# LedMatrix-595.net
KiCad netlist of a schematic drawn in EAGLE
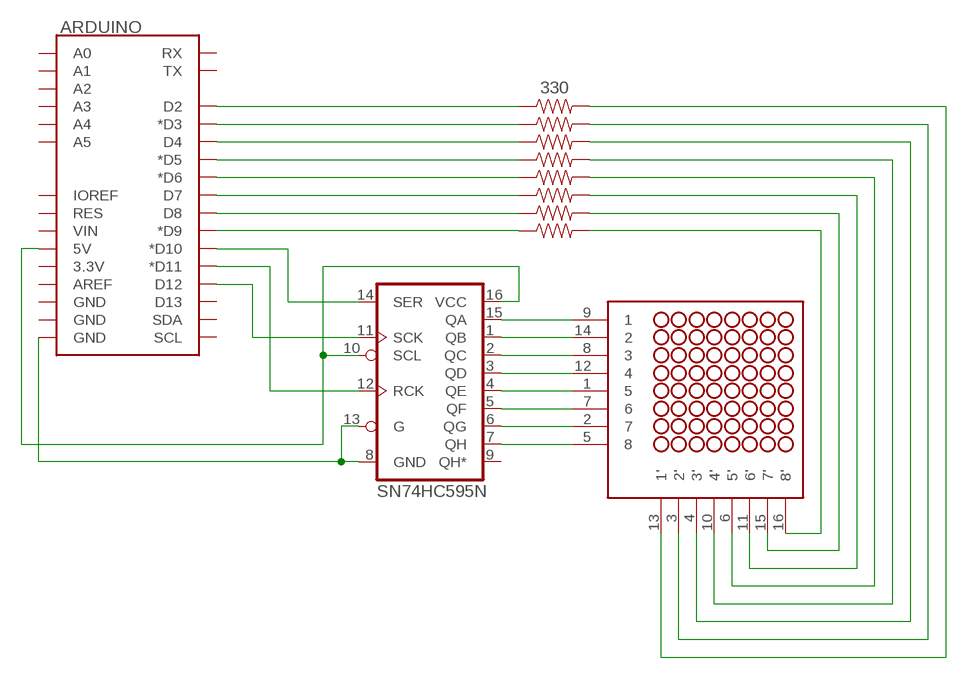
[diagram p0: schematic, sheet 1]

(export (version "E")
  (design (tool "Eeschema 10.0.6"))
  (components
    (comp (ref "ARDUINO")
      (value "ARDUINO_UNO_R3_SHIELDBASIC")
      (footprint "eagle-import:UNO_R3_SHIELD")
      (libsource (lib "eagle-import") (part "ARDUINO_UNO_R3_SHIELDBASIC"))
    )
    (comp (ref "R1")
      (value "330")
      (footprint "eagle-import:AXIAL-0.3")
      (libsource (lib "eagle-import") (part "330OHM-HORIZ-1/10W-5%"))
    )
    (comp (ref "R2")
      (value "330")
      (footprint "eagle-import:AXIAL-0.3")
      (libsource (lib "eagle-import") (part "330OHM-HORIZ-1/10W-5%"))
    )
    (comp (ref "R3")
      (value "330")
      (footprint "eagle-import:AXIAL-0.3")
      (libsource (lib "eagle-import") (part "330OHM-HORIZ-1/10W-5%"))
    )
    (comp (ref "R4")
      (value "330")
      (footprint "eagle-import:AXIAL-0.3")
      (libsource (lib "eagle-import") (part "330OHM-HORIZ-1/10W-5%"))
    )
    (comp (ref "R5")
      (value "330")
      (footprint "eagle-import:AXIAL-0.3")
      (libsource (lib "eagle-import") (part "330OHM-HORIZ-1/10W-5%"))
    )
    (comp (ref "R6")
      (value "330")
      (footprint "eagle-import:AXIAL-0.3")
      (libsource (lib "eagle-import") (part "330OHM-HORIZ-1/10W-5%"))
    )
    (comp (ref "R7")
      (value "330")
      (footprint "eagle-import:AXIAL-0.3")
      (libsource (lib "eagle-import") (part "330OHM-HORIZ-1/10W-5%"))
    )
    (comp (ref "R8")
      (value "330")
      (footprint "eagle-import:AXIAL-0.3")
      (libsource (lib "eagle-import") (part "330OHM-HORIZ-1/10W-5%"))
    )
    (comp (ref "U$1")
      (value "NFM-12881BG-11")
      (footprint "eagle-import:NFM-12881BG-11")
      (libsource (lib "eagle-import") (part "NFM-12881BG-11"))
    )
    (comp (ref "U1")
      (value "SN74HC595N")
      (footprint "eagle-import:DIP16")
      (libsource (lib "eagle-import") (part "74595NHC"))
    )
  )
  (nets
    (net (code "1") (name "Net-(ARDUINO-*D3)") (class "Default")
      (node (ref "ARDUINO") (pin "D3") (pinfunction "*D3_D3") (pintype "bidirectional"))
      (node (ref "R2") (pin "P$1") (pinfunction "1_P$1") (pintype "passive"))
    )
    (net (code "2") (name "Net-(ARDUINO-*D5)") (class "Default")
      (node (ref "ARDUINO") (pin "D5") (pinfunction "*D5_D5") (pintype "bidirectional"))
      (node (ref "R4") (pin "P$1") (pinfunction "1_P$1") (pintype "passive"))
    )
    (net (code "3") (name "Net-(ARDUINO-*D6)") (class "Default")
      (node (ref "ARDUINO") (pin "D6") (pinfunction "*D6_D6") (pintype "bidirectional"))
      (node (ref "R5") (pin "P$1") (pinfunction "1_P$1") (pintype "passive"))
    )
    (net (code "4") (name "Net-(ARDUINO-*D9)") (class "Default")
      (node (ref "ARDUINO") (pin "D9") (pinfunction "*D9_D9") (pintype "bidirectional"))
      (node (ref "R8") (pin "P$1") (pinfunction "1_P$1") (pintype "passive"))
    )
    (net (code "5") (name "Net-(ARDUINO-*D10)") (class "Default")
      (node (ref "ARDUINO") (pin "D10") (pinfunction "*D10_D10") (pintype "bidirectional"))
      (node (ref "U1") (pin "14") (pinfunction "SER_14") (pintype "input"))
    )
    (net (code "6") (name "Net-(ARDUINO-*D11)") (class "Default")
      (node (ref "ARDUINO") (pin "D11") (pinfunction "*D11_D11") (pintype "bidirectional"))
      (node (ref "U1") (pin "12") (pinfunction "RCK_12") (pintype "input"))
    )
    (net (code "7") (name "Net-(R1-1)") (class "Default")
      (node (ref "ARDUINO") (pin "D2") (pinfunction "D2_D2") (pintype "bidirectional"))
      (node (ref "R1") (pin "P$1") (pinfunction "1_P$1") (pintype "passive"))
    )
    (net (code "8") (name "Net-(R1-2)") (class "Default")
      (node (ref "R1") (pin "P$2") (pinfunction "2_P$2") (pintype "passive"))
      (node (ref "U$1") (pin "13") (pinfunction "1'_13") (pintype "output"))
    )
    (net (code "9") (name "Net-(R2-2)") (class "Default")
      (node (ref "R2") (pin "P$2") (pinfunction "2_P$2") (pintype "passive"))
      (node (ref "U$1") (pin "3") (pinfunction "2'_3") (pintype "output"))
    )
    (net (code "10") (name "Net-(R3-1)") (class "Default")
      (node (ref "ARDUINO") (pin "D4") (pinfunction "D4_D4") (pintype "bidirectional"))
      (node (ref "R3") (pin "P$1") (pinfunction "1_P$1") (pintype "passive"))
    )
    (net (code "11") (name "Net-(R3-2)") (class "Default")
      (node (ref "R3") (pin "P$2") (pinfunction "2_P$2") (pintype "passive"))
      (node (ref "U$1") (pin "4") (pinfunction "3'_4") (pintype "output"))
    )
    (net (code "12") (name "Net-(R4-2)") (class "Default")
      (node (ref "R4") (pin "P$2") (pinfunction "2_P$2") (pintype "passive"))
      (node (ref "U$1") (pin "10") (pinfunction "4'_10") (pintype "output"))
    )
    (net (code "13") (name "Net-(R5-2)") (class "Default")
      (node (ref "R5") (pin "P$2") (pinfunction "2_P$2") (pintype "passive"))
      (node (ref "U$1") (pin "6") (pinfunction "5'_6") (pintype "output"))
    )
    (net (code "14") (name "Net-(R6-1)") (class "Default")
      (node (ref "ARDUINO") (pin "D7") (pinfunction "D7_D7") (pintype "bidirectional"))
      (node (ref "R6") (pin "P$1") (pinfunction "1_P$1") (pintype "passive"))
    )
    (net (code "15") (name "Net-(R6-2)") (class "Default")
      (node (ref "R6") (pin "P$2") (pinfunction "2_P$2") (pintype "passive"))
      (node (ref "U$1") (pin "11") (pinfunction "6'_11") (pintype "output"))
    )
    (net (code "16") (name "Net-(R7-1)") (class "Default")
      (node (ref "ARDUINO") (pin "D8") (pinfunction "D8_D8") (pintype "bidirectional"))
      (node (ref "R7") (pin "P$1") (pinfunction "1_P$1") (pintype "passive"))
    )
    (net (code "17") (name "Net-(R7-2)") (class "Default")
      (node (ref "R7") (pin "P$2") (pinfunction "2_P$2") (pintype "passive"))
      (node (ref "U$1") (pin "15") (pinfunction "7'_15") (pintype "output"))
    )
    (net (code "18") (name "Net-(R8-2)") (class "Default")
      (node (ref "R8") (pin "P$2") (pinfunction "2_P$2") (pintype "passive"))
      (node (ref "U$1") (pin "16") (pinfunction "8'_16") (pintype "output"))
    )
    (net (code "19") (name "Net-(U$1-1)") (class "Default")
      (node (ref "U$1") (pin "9") (pinfunction "1_9") (pintype "input"))
      (node (ref "U1") (pin "15") (pinfunction "QA_15") (pintype "tri_state"))
    )
    (net (code "20") (name "Net-(U$1-2)") (class "Default")
      (node (ref "U$1") (pin "14") (pinfunction "2_14") (pintype "input"))
      (node (ref "U1") (pin "1") (pinfunction "QB_1") (pintype "tri_state"))
    )
    (net (code "21") (name "Net-(U$1-3)") (class "Default")
      (node (ref "U$1") (pin "8") (pinfunction "3_8") (pintype "input"))
      (node (ref "U1") (pin "2") (pinfunction "QC_2") (pintype "tri_state"))
    )
    (net (code "22") (name "Net-(U$1-4)") (class "Default")
      (node (ref "U$1") (pin "12") (pinfunction "4_12") (pintype "input"))
      (node (ref "U1") (pin "3") (pinfunction "QD_3") (pintype "tri_state"))
    )
    (net (code "23") (name "Net-(U$1-5)") (class "Default")
      (node (ref "U$1") (pin "1") (pinfunction "5_1") (pintype "input"))
      (node (ref "U1") (pin "4") (pinfunction "QE_4") (pintype "tri_state"))
    )
    (net (code "24") (name "Net-(U$1-6)") (class "Default")
      (node (ref "U$1") (pin "7") (pinfunction "6_7") (pintype "input"))
      (node (ref "U1") (pin "5") (pinfunction "QF_5") (pintype "tri_state"))
    )
    (net (code "25") (name "Net-(U$1-7)") (class "Default")
      (node (ref "U$1") (pin "2") (pinfunction "7_2") (pintype "input"))
      (node (ref "U1") (pin "6") (pinfunction "QG_6") (pintype "tri_state"))
    )
    (net (code "26") (name "Net-(U$1-8)") (class "Default")
      (node (ref "U$1") (pin "5") (pinfunction "8_5") (pintype "input"))
      (node (ref "U1") (pin "7") (pinfunction "QH_7") (pintype "tri_state"))
    )
    (net (code "27") (name "Net-(U1-G)") (class "Default")
      (node (ref "ARDUINO") (pin "GND@0") (pinfunction "GND_GND@0") (pintype "bidirectional"))
      (node (ref "U1") (pin "13") (pinfunction "G_13") (pintype "input"))
      (node (ref "U1") (pin "8") (pinfunction "GND_8") (pintype "power_in"))
    )
    (net (code "28") (name "Net-(U1-SCK)") (class "Default")
      (node (ref "ARDUINO") (pin "D12") (pinfunction "D12_D12") (pintype "bidirectional"))
      (node (ref "U1") (pin "11") (pinfunction "SCK_11") (pintype "input"))
    )
    (net (code "29") (name "Net-(U1-SCL)") (class "Default")
      (node (ref "ARDUINO") (pin "5V") (pinfunction "5V_5V") (pintype "bidirectional"))
      (node (ref "U1") (pin "10") (pinfunction "SCL_10") (pintype "input"))
      (node (ref "U1") (pin "16") (pinfunction "VCC_16") (pintype "power_in"))
    )
    (net (code "30") (name "unconnected-(ARDUINO-GND-PadGND@1)") (class "Default")
      (node (ref "ARDUINO") (pin "GND@1") (pinfunction "GND_GND@1") (pintype "bidirectional"))
    )
    (net (code "31") (name "unconnected-(ARDUINO-GND-PadGND@2)") (class "Default")
      (node (ref "ARDUINO") (pin "GND@2") (pinfunction "GND_GND@2") (pintype "bidirectional"))
    )
    (net (code "32") (name "unconnected-(ARDUINO-Pad3.3V)") (class "Default")
      (node (ref "ARDUINO") (pin "3.3V") (pinfunction "3.3V_3.3V") (pintype "bidirectional"))
    )
    (net (code "33") (name "unconnected-(ARDUINO-PadA0)") (class "Default")
      (node (ref "ARDUINO") (pin "A0") (pinfunction "A0_A0") (pintype "bidirectional"))
    )
    (net (code "34") (name "unconnected-(ARDUINO-PadA1)") (class "Default")
      (node (ref "ARDUINO") (pin "A1") (pinfunction "A1_A1") (pintype "bidirectional"))
    )
    (net (code "35") (name "unconnected-(ARDUINO-PadA2)") (class "Default")
      (node (ref "ARDUINO") (pin "A2") (pinfunction "A2_A2") (pintype "bidirectional"))
    )
    (net (code "36") (name "unconnected-(ARDUINO-PadA3)") (class "Default")
      (node (ref "ARDUINO") (pin "A3") (pinfunction "A3_A3") (pintype "bidirectional"))
    )
    (net (code "37") (name "unconnected-(ARDUINO-PadA4)") (class "Default")
      (node (ref "ARDUINO") (pin "A4") (pinfunction "A4_A4") (pintype "bidirectional"))
    )
    (net (code "38") (name "unconnected-(ARDUINO-PadA5)") (class "Default")
      (node (ref "ARDUINO") (pin "A5") (pinfunction "A5_A5") (pintype "bidirectional"))
    )
    (net (code "39") (name "unconnected-(ARDUINO-PadAREF)") (class "Default")
      (node (ref "ARDUINO") (pin "AREF") (pinfunction "AREF_AREF") (pintype "bidirectional"))
    )
    (net (code "40") (name "unconnected-(ARDUINO-PadD13)") (class "Default")
      (node (ref "ARDUINO") (pin "D13") (pinfunction "D13_D13") (pintype "bidirectional"))
    )
    (net (code "41") (name "unconnected-(ARDUINO-PadIOREF)") (class "Default")
      (node (ref "ARDUINO") (pin "IOREF") (pinfunction "IOREF_IOREF") (pintype "bidirectional"))
    )
    (net (code "42") (name "unconnected-(ARDUINO-PadRES)") (class "Default")
      (node (ref "ARDUINO") (pin "RES") (pinfunction "RES_RES") (pintype "bidirectional"))
    )
    (net (code "43") (name "unconnected-(ARDUINO-PadRX)") (class "Default")
      (node (ref "ARDUINO") (pin "RX") (pinfunction "RX_RX") (pintype "bidirectional"))
    )
    (net (code "44") (name "unconnected-(ARDUINO-PadSCL)") (class "Default")
      (node (ref "ARDUINO") (pin "SCL") (pinfunction "SCL_SCL") (pintype "bidirectional"))
    )
    (net (code "45") (name "unconnected-(ARDUINO-PadSDA)") (class "Default")
      (node (ref "ARDUINO") (pin "SDA") (pinfunction "SDA_SDA") (pintype "bidirectional"))
    )
    (net (code "46") (name "unconnected-(ARDUINO-PadTX)") (class "Default")
      (node (ref "ARDUINO") (pin "TX") (pinfunction "TX_TX") (pintype "bidirectional"))
    )
    (net (code "47") (name "unconnected-(ARDUINO-PadVIN)") (class "Default")
      (node (ref "ARDUINO") (pin "VIN") (pinfunction "VIN_VIN") (pintype "bidirectional"))
    )
    (net (code "48") (name "unconnected-(U1-QH*-Pad9)") (class "Default")
      (node (ref "U1") (pin "9") (pinfunction "QH*_9") (pintype "tri_state"))
    )
  )
)
